# ADC_HUB.net
KiCad netlist of a schematic drawn in Altium Designer
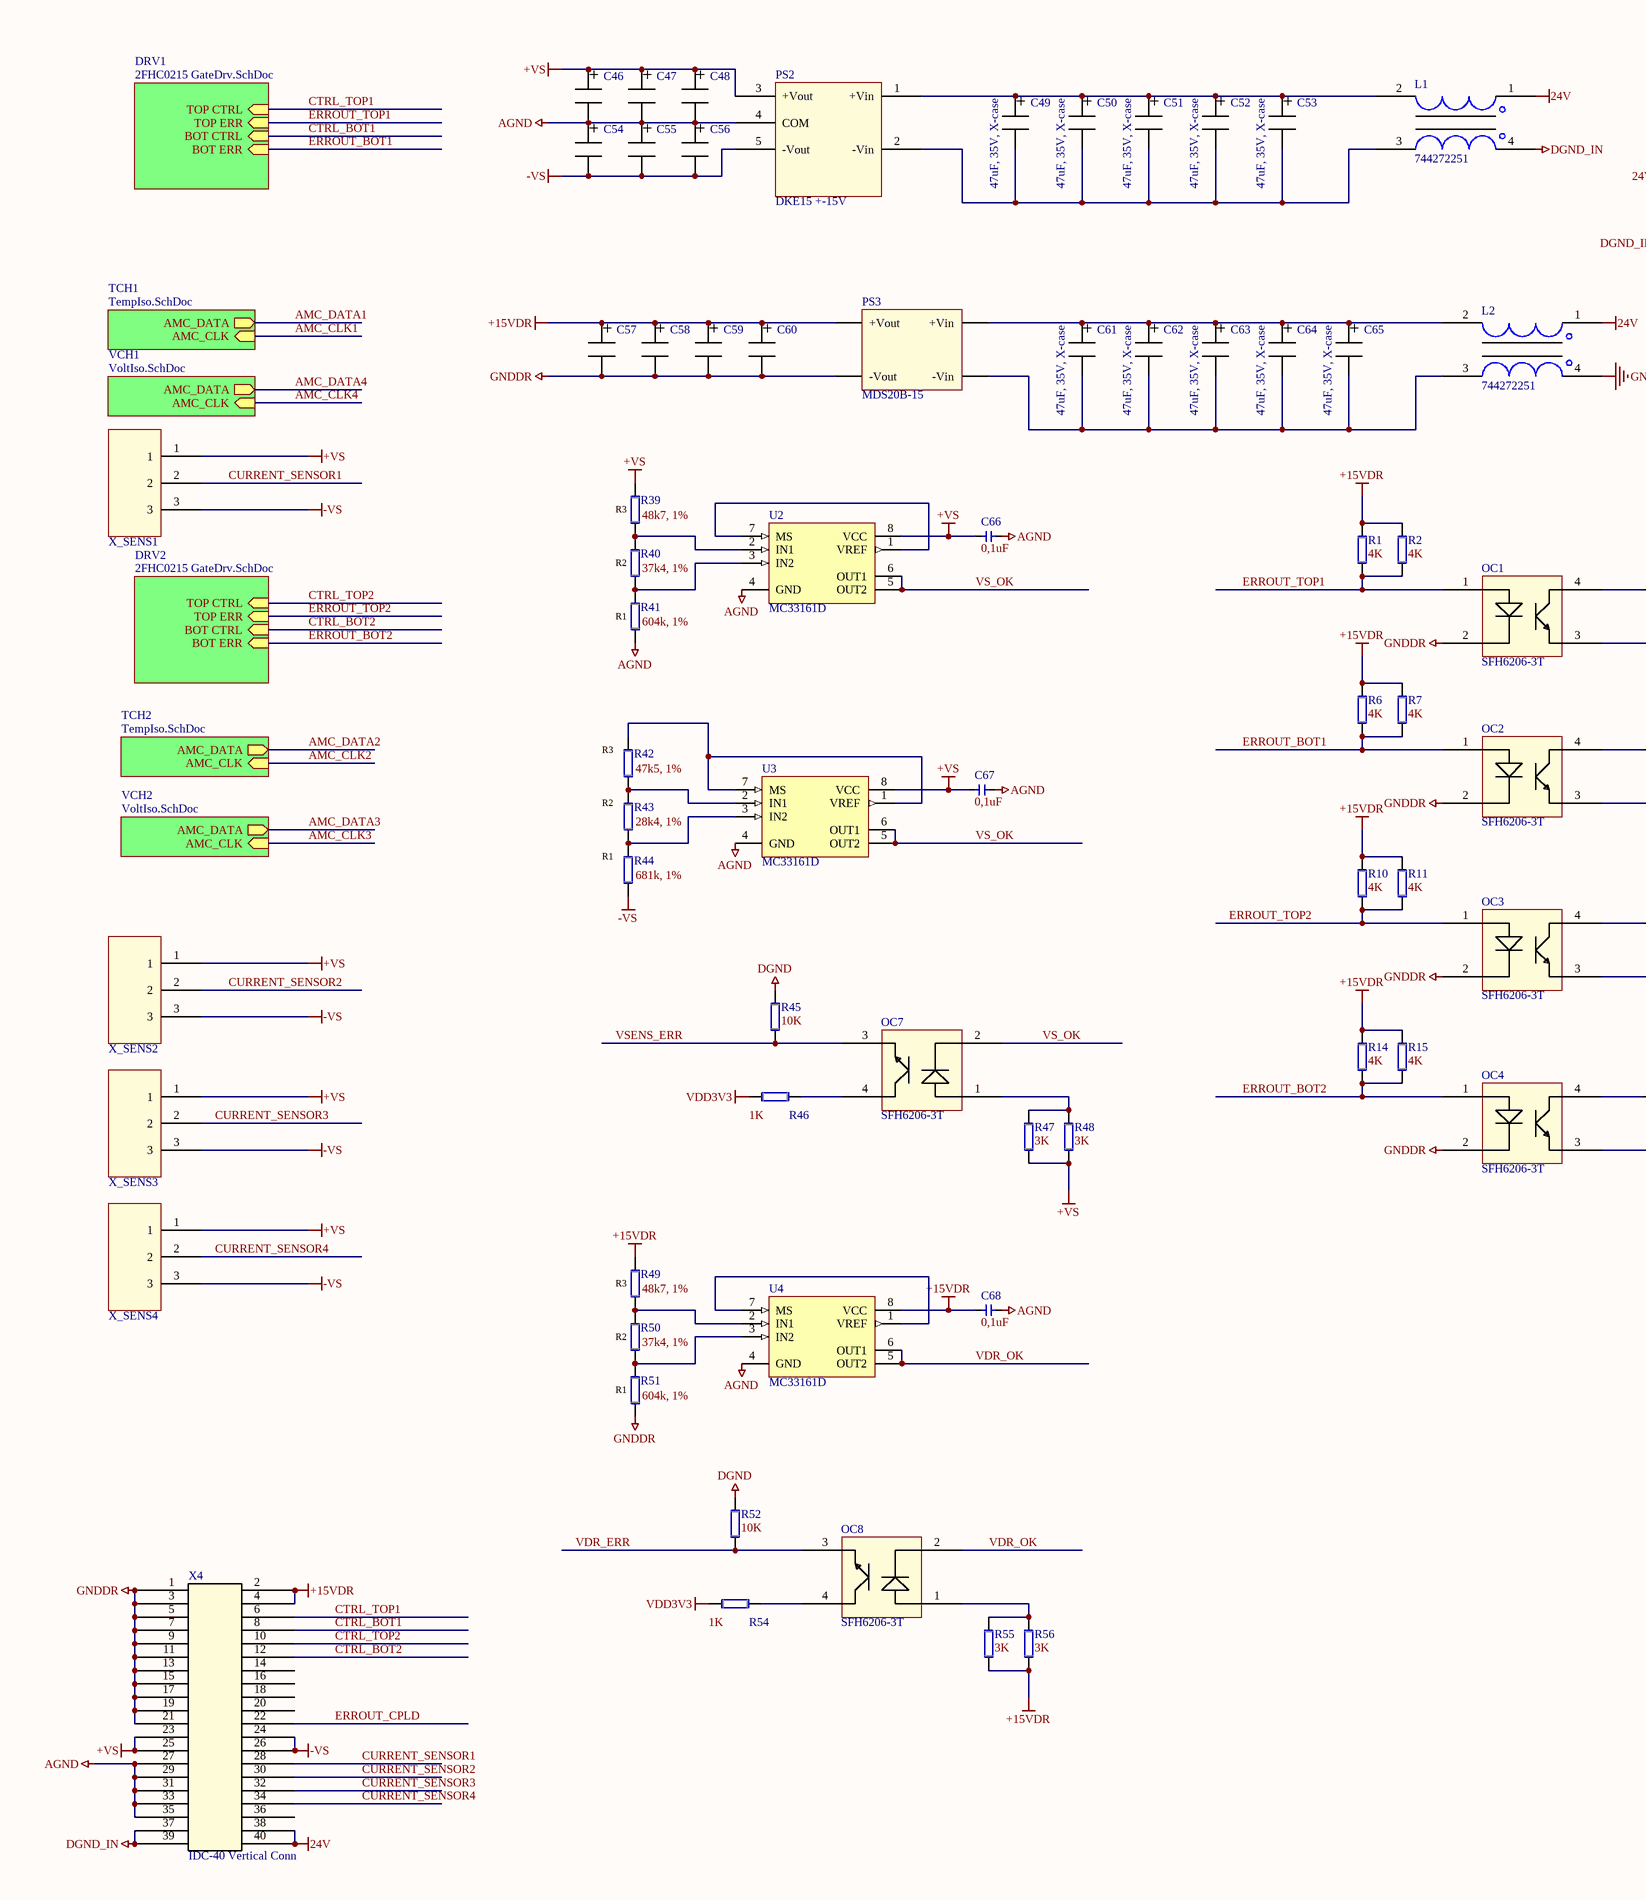
[diagram p0: ADC_HUB.SchDoc, left]
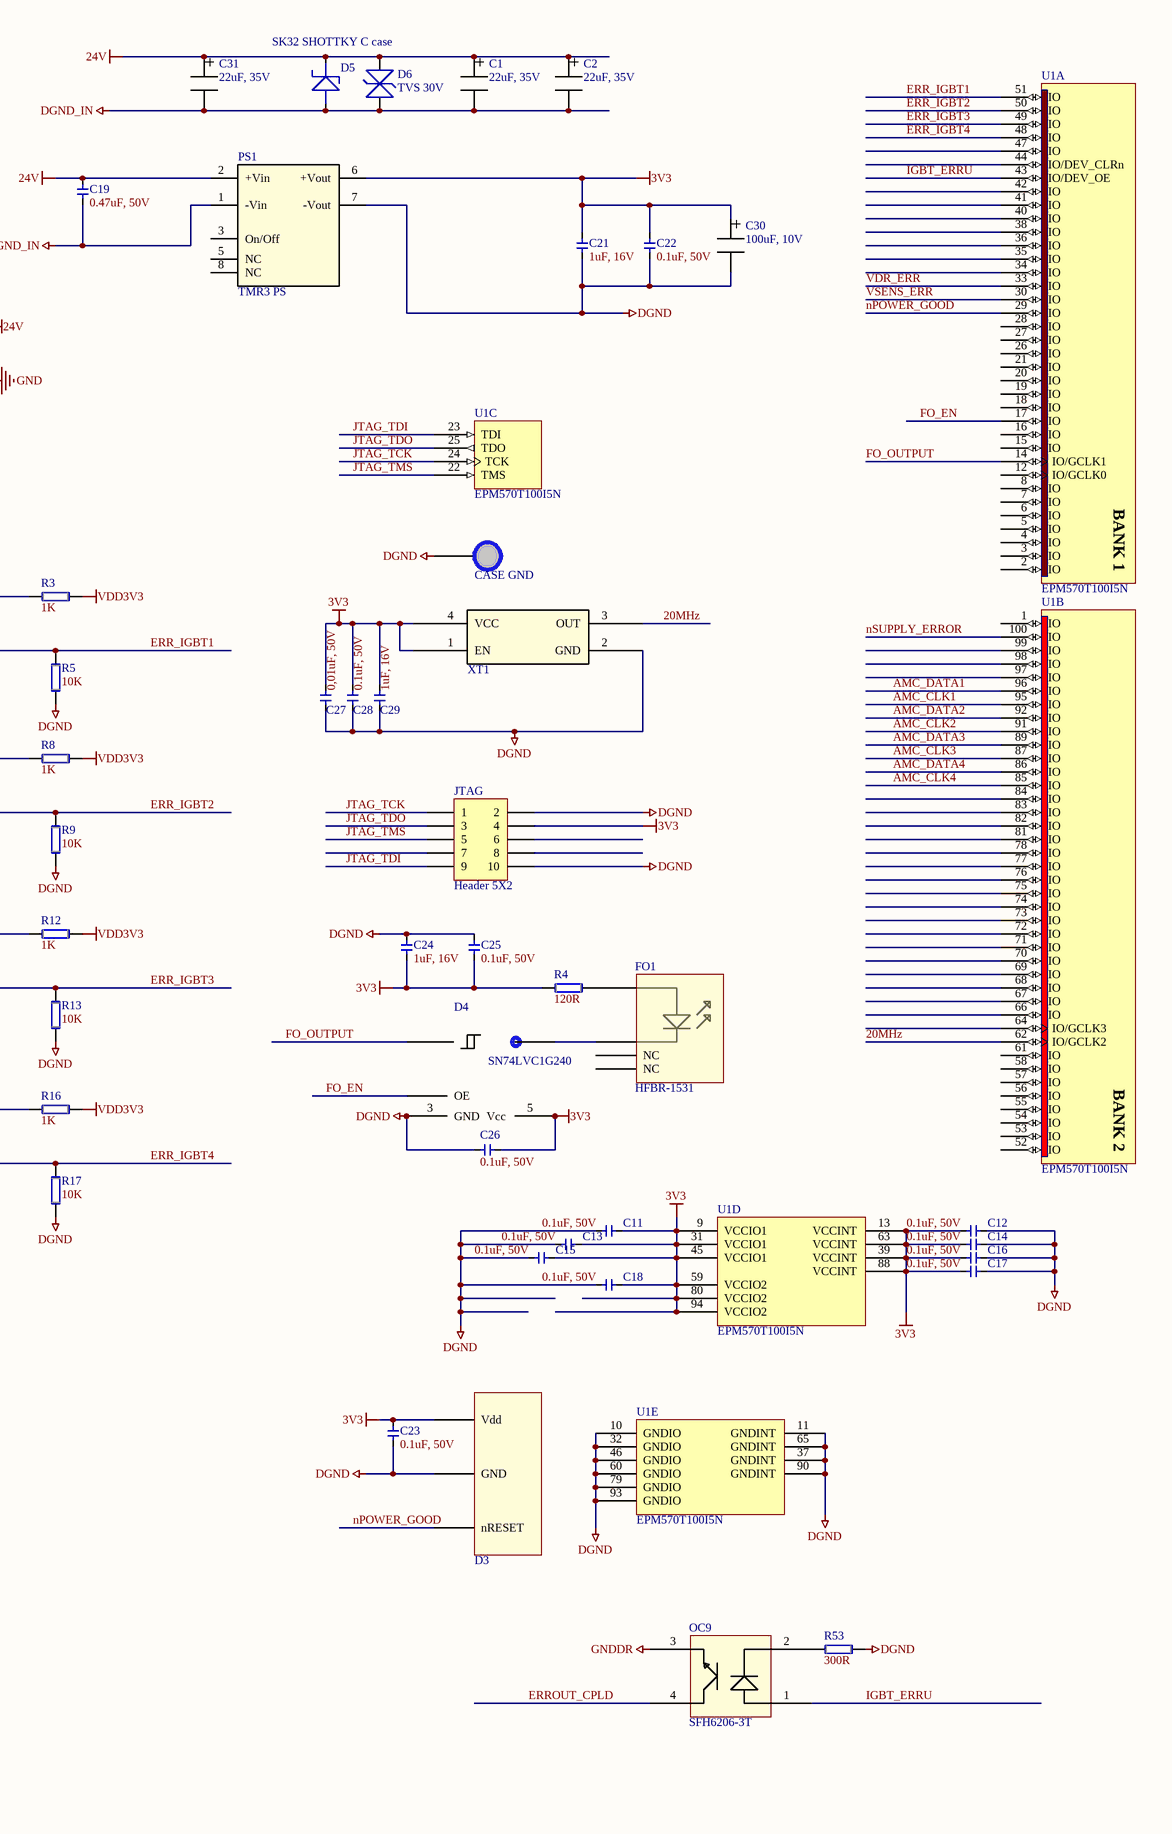
[diagram p1: ADC_HUB.SchDoc, right]

(export (version "E")
  (design (tool "Eeschema 10.0.6"))
  (components
    (comp (ref "C1")
      (value "22uF, 35V")
      (footprint "D")
      (fields (field (name "Comment") "Tant Cap D-case"))
      (libsource (lib "MyLib1") (part "C"))
    )
    (comp (ref "C2")
      (value "22uF, 35V")
      (footprint "D")
      (fields (field (name "Comment") "Tant Cap D-case"))
      (libsource (lib "MyLib1") (part "C"))
    )
    (comp (ref "C11")
      (value "0.1uF, 50V")
      (footprint "SMD CAP 0805")
      (fields (field (name "Comment") "ChipCap"))
      (libsource (lib "MyLib1") (part "ChipCapacitor"))
    )
    (comp (ref "C12")
      (value "0.1uF, 50V")
      (footprint "SMD CAP 0805")
      (fields (field (name "Comment") "ChipCap"))
      (libsource (lib "MyLib1") (part "ChipCapacitor"))
    )
    (comp (ref "C13")
      (value "0.1uF, 50V")
      (footprint "SMD CAP 0805")
      (fields (field (name "Comment") "ChipCap"))
      (libsource (lib "MyLib1") (part "ChipCapacitor"))
    )
    (comp (ref "C14")
      (value "0.1uF, 50V")
      (footprint "SMD CAP 0805")
      (fields (field (name "Comment") "ChipCap"))
      (libsource (lib "MyLib1") (part "ChipCapacitor"))
    )
    (comp (ref "C15")
      (value "0.1uF, 50V")
      (footprint "SMD CAP 0805")
      (fields (field (name "Comment") "ChipCap"))
      (libsource (lib "MyLib1") (part "ChipCapacitor"))
    )
    (comp (ref "C16")
      (value "0.1uF, 50V")
      (footprint "SMD CAP 0805")
      (fields (field (name "Comment") "ChipCap"))
      (libsource (lib "MyLib1") (part "ChipCapacitor"))
    )
    (comp (ref "C17")
      (value "0.1uF, 50V")
      (footprint "SMD CAP 0805")
      (fields (field (name "Comment") "ChipCap"))
      (libsource (lib "MyLib1") (part "ChipCapacitor"))
    )
    (comp (ref "C18")
      (value "0.1uF, 50V")
      (footprint "SMD CAP 0805")
      (fields (field (name "Comment") "ChipCap"))
      (libsource (lib "MyLib1") (part "ChipCapacitor"))
    )
    (comp (ref "C19")
      (value "0.47uF, 50V")
      (footprint "SMD CAP 0805")
      (fields (field (name "Comment") "ChipCap"))
      (libsource (lib "MyLib1") (part "ChipCapacitor"))
    )
    (comp (ref "C21")
      (value "1uF, 16V")
      (footprint "SMD CAP 0805")
      (fields (field (name "Comment") "ChipCap"))
      (libsource (lib "MyLib1") (part "ChipCapacitor"))
    )
    (comp (ref "C22")
      (value "0.1uF, 50V")
      (footprint "SMD CAP 0805")
      (fields (field (name "Comment") "ChipCap"))
      (libsource (lib "MyLib1") (part "ChipCapacitor"))
    )
    (comp (ref "C23")
      (value "0.1uF, 50V")
      (footprint "SMD CAP 0805")
      (fields (field (name "Comment") "ChipCap"))
      (libsource (lib "MyLib1") (part "ChipCapacitor"))
    )
    (comp (ref "C24")
      (value "1uF, 16V")
      (footprint "SMD CAP 0805")
      (fields (field (name "Comment") "ChipCap"))
      (libsource (lib "MyLib1") (part "ChipCapacitor"))
    )
    (comp (ref "C25")
      (value "0.1uF, 50V")
      (footprint "SMD CAP 0805")
      (fields (field (name "Comment") "ChipCap"))
      (libsource (lib "MyLib1") (part "ChipCapacitor"))
    )
    (comp (ref "C26")
      (value "0.1uF, 50V")
      (footprint "SMD CAP 0805")
      (fields (field (name "Comment") "ChipCap"))
      (libsource (lib "MyLib1") (part "ChipCapacitor"))
    )
    (comp (ref "C27")
      (value "0,01uF, 50V")
      (footprint "SMD CAP 0805")
      (fields (field (name "Comment") "ChipCap"))
      (libsource (lib "MyLib1") (part "ChipCapacitor"))
    )
    (comp (ref "C28")
      (value "0.1uF, 50V")
      (footprint "SMD CAP 0805")
      (fields (field (name "Comment") "ChipCap"))
      (libsource (lib "MyLib1") (part "ChipCapacitor"))
    )
    (comp (ref "C29")
      (value "1uF, 16V")
      (footprint "SMD CAP 0805")
      (fields (field (name "Comment") "ChipCap"))
      (libsource (lib "MyLib1") (part "ChipCapacitor"))
    )
    (comp (ref "C30")
      (value "100uF, 10V")
      (footprint "D")
      (fields (field (name "Comment") "Tant Cap D-case"))
      (libsource (lib "MyLib1") (part "C"))
    )
    (comp (ref "C31")
      (value "22uF, 35V")
      (footprint "D")
      (fields (field (name "Comment") "Tant Cap D-case"))
      (libsource (lib "MyLib1") (part "C"))
    )
    (comp (ref "C46") (value "Tant Cap D-case") (footprint "D") (libsource (lib "MyLib1") (part "C")))
    (comp (ref "C47") (value "Tant Cap D-case") (footprint "D") (libsource (lib "MyLib1") (part "C")))
    (comp (ref "C48") (value "Tant Cap D-case") (footprint "D") (libsource (lib "MyLib1") (part "C")))
    (comp (ref "C49")
      (value "47uF, 35V, X-case")
      (footprint "X")
      (fields (field (name "Comment") "Tant Cap D-case"))
      (libsource (lib "MyLib1") (part "C"))
    )
    (comp (ref "C50")
      (value "47uF, 35V, X-case")
      (footprint "X")
      (fields (field (name "Comment") "Tant Cap D-case"))
      (libsource (lib "MyLib1") (part "C"))
    )
    (comp (ref "C51")
      (value "47uF, 35V, X-case")
      (footprint "X")
      (fields (field (name "Comment") "Tant Cap D-case"))
      (libsource (lib "MyLib1") (part "C"))
    )
    (comp (ref "C52")
      (value "47uF, 35V, X-case")
      (footprint "X")
      (fields (field (name "Comment") "Tant Cap D-case"))
      (libsource (lib "MyLib1") (part "C"))
    )
    (comp (ref "C53")
      (value "47uF, 35V, X-case")
      (footprint "X")
      (fields (field (name "Comment") "Tant Cap D-case"))
      (libsource (lib "MyLib1") (part "C"))
    )
    (comp (ref "C54") (value "Tant Cap D-case") (footprint "D") (libsource (lib "MyLib1") (part "C")))
    (comp (ref "C55") (value "Tant Cap D-case") (footprint "D") (libsource (lib "MyLib1") (part "C")))
    (comp (ref "C56") (value "Tant Cap D-case") (footprint "D") (libsource (lib "MyLib1") (part "C")))
    (comp (ref "C57") (value "Tant Cap D-case") (footprint "D") (libsource (lib "MyLib1") (part "C")))
    (comp (ref "C58") (value "Tant Cap D-case") (footprint "D") (libsource (lib "MyLib1") (part "C")))
    (comp (ref "C59") (value "Tant Cap D-case") (footprint "D") (libsource (lib "MyLib1") (part "C")))
    (comp (ref "C60") (value "Tant Cap D-case") (footprint "D") (libsource (lib "MyLib1") (part "C")))
    (comp (ref "C61")
      (value "47uF, 35V, X-case")
      (footprint "X")
      (fields (field (name "Comment") "Tant Cap D-case"))
      (libsource (lib "MyLib1") (part "C"))
    )
    (comp (ref "C62")
      (value "47uF, 35V, X-case")
      (footprint "X")
      (fields (field (name "Comment") "Tant Cap D-case"))
      (libsource (lib "MyLib1") (part "C"))
    )
    (comp (ref "C63")
      (value "47uF, 35V, X-case")
      (footprint "X")
      (fields (field (name "Comment") "Tant Cap D-case"))
      (libsource (lib "MyLib1") (part "C"))
    )
    (comp (ref "C64")
      (value "47uF, 35V, X-case")
      (footprint "X")
      (fields (field (name "Comment") "Tant Cap D-case"))
      (libsource (lib "MyLib1") (part "C"))
    )
    (comp (ref "C65")
      (value "47uF, 35V, X-case")
      (footprint "X")
      (fields (field (name "Comment") "Tant Cap D-case"))
      (libsource (lib "MyLib1") (part "C"))
    )
    (comp (ref "C66")
      (value "0,1uF")
      (footprint "SMD CAP 0603")
      (fields (field (name "Comment") "ChipCap"))
      (libsource (lib "MyLib1") (part "ChipCapacitor"))
    )
    (comp (ref "C67")
      (value "0,1uF")
      (footprint "SMD CAP 0603")
      (fields (field (name "Comment") "ChipCap"))
      (libsource (lib "MyLib1") (part "ChipCapacitor"))
    )
    (comp (ref "C68")
      (value "0,1uF")
      (footprint "SMD CAP 0603")
      (fields (field (name "Comment") "ChipCap"))
      (libsource (lib "MyLib1") (part "ChipCapacitor"))
    )
    (comp (ref "CASE GND") (value "PAD 3mm") (footprint "PAD3mm") (libsource (lib "MyLib1") (part "PAD 3mm")))
    (comp (ref "D3")
      (value "TPS3809")
      (footprint "TPS3809")
      (description "Voltage Supervisor")
      (libsource (lib "MyLib1") (part "TPS3809"))
    )
    (comp (ref "D4")
      (value "SN74LVC1G240")
      (footprint "TI-SOT23 SOT95P280X145-5N")
      (description "Inverted Schmitt Trigger with EN")
      (libsource (lib "MyLib1") (part "SN74LVC1G240"))
    )
    (comp (ref "D5")
      (value "SK32 SHOTTKY C case")
      (footprint "SMC DIODE")
      (libsource (lib "MyLib1") (part "SK32 SHOTTKY"))
    )
    (comp (ref "D6")
      (value "TVS 30V")
      (footprint "SMB TVS")
      (libsource (lib "MyLib1") (part "SMB TVS BiDir"))
    )
    (comp (ref "FO1")
      (value "HFBR-1531")
      (footprint "1531/2531")
      (description "Fiber Optical Transmitter")
      (libsource (lib "MyLib1") (part "HFBR-1531"))
    )
    (comp (ref "JTAG")
      (value "Header 5X2")
      (footprint "HDR2X5")
      (description "Header, 5-Pin, Dual row")
      (fields (field (name "PUBLISHER") "Altium Limited"))
      (libsource (lib "Miscellaneous Connectors") (part "Header 5X2"))
    )
    (comp (ref "L1")
      (value "744272251")
      (footprint "744272251")
      (description "Wurth EMI Choke")
      (libsource (lib "MyLib1") (part "Wurth EMI Choke 744272251"))
    )
    (comp (ref "L2")
      (value "744272251")
      (footprint "744272251")
      (description "Wurth EMI Choke")
      (libsource (lib "MyLib1") (part "Wurth EMI Choke 744272251"))
    )
    (comp (ref "OC1")
      (value "SFH6206-3T")
      (footprint "SFH6206-3T")
      (description "SFH6206-3T Optocoupler")
      (libsource (lib "") (part "SFH6206-3T_1"))
    )
    (comp (ref "OC2")
      (value "SFH6206-3T")
      (footprint "SFH6206-3T")
      (description "SFH6206-3T Optocoupler")
      (libsource (lib "") (part "SFH6206-3T_1"))
    )
    (comp (ref "OC3")
      (value "SFH6206-3T")
      (footprint "SFH6206-3T")
      (description "SFH6206-3T Optocoupler")
      (libsource (lib "") (part "SFH6206-3T_1"))
    )
    (comp (ref "OC4")
      (value "SFH6206-3T")
      (footprint "SFH6206-3T")
      (description "SFH6206-3T Optocoupler")
      (libsource (lib "") (part "SFH6206-3T_1"))
    )
    (comp (ref "OC7")
      (value "SFH6206-3T")
      (footprint "SFH6206-3T")
      (description "SFH6206-3T Optocoupler")
      (libsource (lib "MyLib1") (part "SFH6206-3T"))
    )
    (comp (ref "OC8")
      (value "SFH6206-3T")
      (footprint "SFH6206-3T")
      (description "SFH6206-3T Optocoupler")
      (libsource (lib "MyLib1") (part "SFH6206-3T"))
    )
    (comp (ref "OC9")
      (value "SFH6206-3T")
      (footprint "SFH6206-3T")
      (description "SFH6206-3T Optocoupler")
      (libsource (lib "MyLib1") (part "SFH6206-3T"))
    )
    (comp (ref "PS1")
      (value "TMR3 PS")
      (footprint "TMR3 TRACO")
      (description "TMR3 power supply")
      (libsource (lib "MyLib1") (part "TMR3 TRACO"))
    )
    (comp (ref "PS2")
      (value "DKE15 +-15V")
      (footprint "DKE15")
      (description "DKE 15 MW Power Supply")
      (fields (field (name "Comment") "DKE 15 PS"))
      (libsource (lib "MyLib1") (part "DKE15 PS"))
    )
    (comp (ref "PS3")
      (value "MDS20B-15")
      (footprint "MDS20B-15")
      (description "MDS20B-15  power supply 15V")
      (libsource (lib "MyLib1") (part "MDS20B-15"))
    )
    (comp (ref "R1")
      (value "4K")
      (footprint "R1206")
      (fields (field (name "Comment") "Rsize"))
      (libsource (lib "MyLib1") (part "ChipResistor"))
    )
    (comp (ref "R2")
      (value "4K")
      (footprint "R1206")
      (fields (field (name "Comment") "Rsize"))
      (libsource (lib "MyLib1") (part "ChipResistor"))
    )
    (comp (ref "R3")
      (value "1K")
      (footprint "SMD RES 0805")
      (fields (field (name "Comment") "Rsize"))
      (libsource (lib "MyLib1") (part "ChipResistor"))
    )
    (comp (ref "R4")
      (value "120R")
      (footprint "SMD RES 0805")
      (fields (field (name "Comment") "Rsize"))
      (libsource (lib "MyLib1") (part "ChipResistor"))
    )
    (comp (ref "R5")
      (value "10K")
      (footprint "SMD RES 0805")
      (fields (field (name "Comment") "Rsize"))
      (libsource (lib "MyLib1") (part "ChipResistor"))
    )
    (comp (ref "R6")
      (value "4K")
      (footprint "R1206")
      (fields (field (name "Comment") "Rsize"))
      (libsource (lib "MyLib1") (part "ChipResistor"))
    )
    (comp (ref "R7")
      (value "4K")
      (footprint "R1206")
      (fields (field (name "Comment") "Rsize"))
      (libsource (lib "MyLib1") (part "ChipResistor"))
    )
    (comp (ref "R8")
      (value "1K")
      (footprint "SMD RES 0805")
      (fields (field (name "Comment") "Rsize"))
      (libsource (lib "MyLib1") (part "ChipResistor"))
    )
    (comp (ref "R9")
      (value "10K")
      (footprint "SMD RES 0805")
      (fields (field (name "Comment") "Rsize"))
      (libsource (lib "MyLib1") (part "ChipResistor"))
    )
    (comp (ref "R10")
      (value "4K")
      (footprint "R1206")
      (fields (field (name "Comment") "Rsize"))
      (libsource (lib "MyLib1") (part "ChipResistor"))
    )
    (comp (ref "R11")
      (value "4K")
      (footprint "R1206")
      (fields (field (name "Comment") "Rsize"))
      (libsource (lib "MyLib1") (part "ChipResistor"))
    )
    (comp (ref "R12")
      (value "1K")
      (footprint "SMD RES 0805")
      (fields (field (name "Comment") "Rsize"))
      (libsource (lib "MyLib1") (part "ChipResistor"))
    )
    (comp (ref "R13")
      (value "10K")
      (footprint "SMD RES 0805")
      (fields (field (name "Comment") "Rsize"))
      (libsource (lib "MyLib1") (part "ChipResistor"))
    )
    (comp (ref "R14")
      (value "4K")
      (footprint "R1206")
      (fields (field (name "Comment") "Rsize"))
      (libsource (lib "MyLib1") (part "ChipResistor"))
    )
    (comp (ref "R15")
      (value "4K")
      (footprint "R1206")
      (fields (field (name "Comment") "Rsize"))
      (libsource (lib "MyLib1") (part "ChipResistor"))
    )
    (comp (ref "R16")
      (value "1K")
      (footprint "SMD RES 0805")
      (fields (field (name "Comment") "Rsize"))
      (libsource (lib "MyLib1") (part "ChipResistor"))
    )
    (comp (ref "R17")
      (value "10K")
      (footprint "SMD RES 0805")
      (fields (field (name "Comment") "Rsize"))
      (libsource (lib "MyLib1") (part "ChipResistor"))
    )
    (comp (ref "R39")
      (value "48k7, 1%")
      (footprint "SMD RES 0603")
      (fields (field (name "Comment") "Rsize"))
      (libsource (lib "MyLib1") (part "ChipResistor"))
    )
    (comp (ref "R40")
      (value "37k4, 1%")
      (footprint "SMD RES 0603")
      (fields (field (name "Comment") "Rsize"))
      (libsource (lib "MyLib1") (part "ChipResistor"))
    )
    (comp (ref "R41")
      (value "604k, 1%")
      (footprint "SMD RES 0603")
      (fields (field (name "Comment") "Rsize"))
      (libsource (lib "MyLib1") (part "ChipResistor"))
    )
    (comp (ref "R42")
      (value "47k5, 1%")
      (footprint "SMD RES 0603")
      (fields (field (name "Comment") "Rsize"))
      (libsource (lib "MyLib1") (part "ChipResistor"))
    )
    (comp (ref "R43")
      (value "28k4, 1%")
      (footprint "SMD RES 0603")
      (fields (field (name "Comment") "Rsize"))
      (libsource (lib "MyLib1") (part "ChipResistor"))
    )
    (comp (ref "R44")
      (value "681k, 1%")
      (footprint "SMD RES 0603")
      (fields (field (name "Comment") "Rsize"))
      (libsource (lib "MyLib1") (part "ChipResistor"))
    )
    (comp (ref "R45")
      (value "10K")
      (footprint "SMD RES 0805")
      (fields (field (name "Comment") "Rsize"))
      (libsource (lib "MyLib1") (part "ChipResistor"))
    )
    (comp (ref "R46")
      (value "1K")
      (footprint "SMD RES 0805")
      (fields (field (name "Comment") "Rsize"))
      (libsource (lib "MyLib1") (part "ChipResistor"))
    )
    (comp (ref "R47")
      (value "3K")
      (footprint "R1206")
      (fields (field (name "Comment") "Rsize"))
      (libsource (lib "MyLib1") (part "ChipResistor"))
    )
    (comp (ref "R48")
      (value "3K")
      (footprint "R1206")
      (fields (field (name "Comment") "Rsize"))
      (libsource (lib "MyLib1") (part "ChipResistor"))
    )
    (comp (ref "R49")
      (value "48k7, 1%")
      (footprint "SMD RES 0603")
      (fields (field (name "Comment") "Rsize"))
      (libsource (lib "MyLib1") (part "ChipResistor"))
    )
    (comp (ref "R50")
      (value "37k4, 1%")
      (footprint "SMD RES 0603")
      (fields (field (name "Comment") "Rsize"))
      (libsource (lib "MyLib1") (part "ChipResistor"))
    )
    (comp (ref "R51")
      (value "604k, 1%")
      (footprint "SMD RES 0603")
      (fields (field (name "Comment") "Rsize"))
      (libsource (lib "MyLib1") (part "ChipResistor"))
    )
    (comp (ref "R52")
      (value "10K")
      (footprint "SMD RES 0805")
      (fields (field (name "Comment") "Rsize"))
      (libsource (lib "MyLib1") (part "ChipResistor"))
    )
    (comp (ref "R53")
      (value "300R")
      (footprint "R1206")
      (fields (field (name "Comment") "Rsize"))
      (libsource (lib "MyLib1") (part "ChipResistor"))
    )
    (comp (ref "R54")
      (value "1K")
      (footprint "SMD RES 0805")
      (fields (field (name "Comment") "Rsize"))
      (libsource (lib "MyLib1") (part "ChipResistor"))
    )
    (comp (ref "R55")
      (value "3K")
      (footprint "R1206")
      (fields (field (name "Comment") "Rsize"))
      (libsource (lib "MyLib1") (part "ChipResistor"))
    )
    (comp (ref "R56")
      (value "3K")
      (footprint "R1206")
      (fields (field (name "Comment") "Rsize"))
      (libsource (lib "MyLib1") (part "ChipResistor"))
    )
    (comp (ref "U1")
      (value "EPM570T100I5N")
      (footprint "TQFP100_N")
      (fields (field (name "PUBLISHER") "Altium Limited"))
      (libsource (lib "Altera MAX II") (part "EPM570T100I5N"))
    )
    (comp (ref "U2")
      (value "MC33161D")
      (footprint "751-05_N")
      (description "Universal Voltage Monitor")
      (fields (field (name "PUBLISHER") "Altium Limited"))
      (libsource (lib "ON Semi Power Mgt Voltage Detector") (part "MC33161D"))
    )
    (comp (ref "U3")
      (value "MC33161D")
      (footprint "751-05_N")
      (description "Universal Voltage Monitor")
      (fields (field (name "PUBLISHER") "Altium Limited"))
      (libsource (lib "ON Semi Power Mgt Voltage Detector") (part "MC33161D"))
    )
    (comp (ref "U4")
      (value "MC33161D")
      (footprint "751-05_N")
      (description "Universal Voltage Monitor")
      (fields (field (name "PUBLISHER") "Altium Limited"))
      (libsource (lib "ON Semi Power Mgt Voltage Detector") (part "MC33161D"))
    )
    (comp (ref "X4")
      (value "IDC-40 Vertical Conn")
      (footprint "IDC2.54-V40")
      (libsource (lib "MyLib1") (part "IDC-40"))
    )
    (comp (ref "XT1")
      (value "Crystal generator")
      (footprint "OSC3225 YXC")
      (libsource (lib "MyLib1") (part "GEN 0532"))
    )
    (comp (ref "X_SENS1")
      (value "Connector 3.5mm")
      (footprint "15EDGRC-3.5 3P")
      (libsource (lib "MyLib1") (part "15EDGRC-3.5 3P"))
    )
    (comp (ref "X_SENS2")
      (value "Connector 3.5mm")
      (footprint "15EDGRC-3.5 3P")
      (libsource (lib "MyLib1") (part "15EDGRC-3.5 3P"))
    )
    (comp (ref "X_SENS3")
      (value "Connector 3.5mm")
      (footprint "15EDGRC-3.5 3P")
      (libsource (lib "MyLib1") (part "15EDGRC-3.5 3P"))
    )
    (comp (ref "X_SENS4")
      (value "Connector 3.5mm")
      (footprint "15EDGRC-3.5 3P")
      (libsource (lib "MyLib1") (part "15EDGRC-3.5 3P"))
    )
  )
  (nets
    (net (code "1") (name "+15VDR") (class "Default")
      (node (ref "C57") (pin "1") (pinfunction "1_1") (pintype "passive"))
      (node (ref "C58") (pin "1") (pinfunction "1_1") (pintype "passive"))
      (node (ref "C59") (pin "1") (pinfunction "1_1") (pintype "passive"))
      (node (ref "C60") (pin "1") (pinfunction "1_1") (pintype "passive"))
      (node (ref "C68") (pin "2") (pinfunction "2_2") (pintype "passive"))
      (node (ref "PS3") (pin "3") (pinfunction "+Vout_3") (pintype "passive"))
      (node (ref "R1") (pin "1") (pinfunction "1_1") (pintype "passive"))
      (node (ref "R10") (pin "1") (pinfunction "1_1") (pintype "passive"))
      (node (ref "R11") (pin "1") (pinfunction "1_1") (pintype "passive"))
      (node (ref "R14") (pin "1") (pinfunction "1_1") (pintype "passive"))
      (node (ref "R15") (pin "1") (pinfunction "1_1") (pintype "passive"))
      (node (ref "R2") (pin "1") (pinfunction "1_1") (pintype "passive"))
      (node (ref "R49") (pin "1") (pinfunction "1_1") (pintype "passive"))
      (node (ref "R55") (pin "1") (pinfunction "1_1") (pintype "passive"))
      (node (ref "R56") (pin "1") (pinfunction "1_1") (pintype "passive"))
      (node (ref "R6") (pin "1") (pinfunction "1_1") (pintype "passive"))
      (node (ref "R7") (pin "1") (pinfunction "1_1") (pintype "passive"))
      (node (ref "U4") (pin "8") (pinfunction "VCC_8") (pintype "power_in"))
      (node (ref "X4") (pin "2") (pinfunction "2_2") (pintype "passive"))
      (node (ref "X4") (pin "4") (pinfunction "4_4") (pintype "passive"))
    )
    (net (code "2") (name "+VS") (class "Default")
      (node (ref "C46") (pin "1") (pinfunction "1_1") (pintype "passive"))
      (node (ref "C47") (pin "1") (pinfunction "1_1") (pintype "passive"))
      (node (ref "C48") (pin "1") (pinfunction "1_1") (pintype "passive"))
      (node (ref "C66") (pin "2") (pinfunction "2_2") (pintype "passive"))
      (node (ref "C67") (pin "2") (pinfunction "2_2") (pintype "passive"))
      (node (ref "PS2") (pin "3") (pinfunction "+Vout_3") (pintype "passive"))
      (node (ref "R39") (pin "1") (pinfunction "1_1") (pintype "passive"))
      (node (ref "R47") (pin "1") (pinfunction "1_1") (pintype "passive"))
      (node (ref "R48") (pin "1") (pinfunction "1_1") (pintype "passive"))
      (node (ref "U2") (pin "8") (pinfunction "VCC_8") (pintype "power_in"))
      (node (ref "U3") (pin "8") (pinfunction "VCC_8") (pintype "power_in"))
      (node (ref "X4") (pin "23") (pinfunction "23_23") (pintype "passive"))
      (node (ref "X4") (pin "25") (pinfunction "25_25") (pintype "passive"))
      (node (ref "X_SENS1") (pin "1") (pinfunction "1_1") (pintype "passive"))
      (node (ref "X_SENS2") (pin "1") (pinfunction "1_1") (pintype "passive"))
      (node (ref "X_SENS3") (pin "1") (pinfunction "1_1") (pintype "passive"))
      (node (ref "X_SENS4") (pin "1") (pinfunction "1_1") (pintype "passive"))
    )
    (net (code "3") (name "-VS") (class "Default")
      (node (ref "C54") (pin "2") (pinfunction "2_2") (pintype "passive"))
      (node (ref "C55") (pin "2") (pinfunction "2_2") (pintype "passive"))
      (node (ref "C56") (pin "2") (pinfunction "2_2") (pintype "passive"))
      (node (ref "PS2") (pin "5") (pinfunction "-Vout_5") (pintype "passive"))
      (node (ref "R44") (pin "2") (pinfunction "2_2") (pintype "passive"))
      (node (ref "X4") (pin "24") (pinfunction "24_24") (pintype "passive"))
      (node (ref "X4") (pin "26") (pinfunction "26_26") (pintype "passive"))
      (node (ref "X_SENS1") (pin "3") (pinfunction "3_3") (pintype "passive"))
      (node (ref "X_SENS2") (pin "3") (pinfunction "3_3") (pintype "passive"))
      (node (ref "X_SENS3") (pin "3") (pinfunction "3_3") (pintype "passive"))
      (node (ref "X_SENS4") (pin "3") (pinfunction "3_3") (pintype "passive"))
    )
    (net (code "4") (name "/20MHz") (class "Default")
      (node (ref "U1") (pin "62") (pinfunction "IO/GCLK2_62") (pintype "bidirectional"))
      (node (ref "XT1") (pin "3") (pinfunction "OUT_3") (pintype "passive"))
    )
    (net (code "5") (name "/AMC_CLK1") (class "Default")
      (node (ref "U1") (pin "95") (pinfunction "IO_95") (pintype "bidirectional"))
    )
    (net (code "6") (name "/AMC_CLK2") (class "Default")
      (node (ref "U1") (pin "91") (pinfunction "IO_91") (pintype "bidirectional"))
    )
    (net (code "7") (name "/AMC_CLK3") (class "Default")
      (node (ref "U1") (pin "87") (pinfunction "IO_87") (pintype "bidirectional"))
    )
    (net (code "8") (name "/AMC_CLK4") (class "Default")
      (node (ref "U1") (pin "85") (pinfunction "IO_85") (pintype "bidirectional"))
    )
    (net (code "9") (name "/AMC_DATA1") (class "Default")
      (node (ref "U1") (pin "96") (pinfunction "IO_96") (pintype "bidirectional"))
    )
    (net (code "10") (name "/AMC_DATA2") (class "Default")
      (node (ref "U1") (pin "92") (pinfunction "IO_92") (pintype "bidirectional"))
    )
    (net (code "11") (name "/AMC_DATA3") (class "Default")
      (node (ref "U1") (pin "89") (pinfunction "IO_89") (pintype "bidirectional"))
    )
    (net (code "12") (name "/AMC_DATA4") (class "Default")
      (node (ref "U1") (pin "86") (pinfunction "IO_86") (pintype "bidirectional"))
    )
    (net (code "13") (name "/CTRL_BOT1") (class "Default")
      (node (ref "X4") (pin "8") (pinfunction "8_8") (pintype "passive"))
    )
    (net (code "14") (name "/CTRL_BOT2") (class "Default")
      (node (ref "X4") (pin "12") (pinfunction "12_12") (pintype "passive"))
    )
    (net (code "15") (name "/CTRL_TOP1") (class "Default")
      (node (ref "X4") (pin "6") (pinfunction "6_6") (pintype "passive"))
    )
    (net (code "16") (name "/CTRL_TOP2") (class "Default")
      (node (ref "X4") (pin "10") (pinfunction "10_10") (pintype "passive"))
    )
    (net (code "17") (name "/CURRENT_SENSOR1") (class "Default")
      (node (ref "X4") (pin "28") (pinfunction "28_28") (pintype "passive"))
      (node (ref "X_SENS1") (pin "2") (pinfunction "2_2") (pintype "passive"))
    )
    (net (code "18") (name "/CURRENT_SENSOR2") (class "Default")
      (node (ref "X4") (pin "30") (pinfunction "30_30") (pintype "passive"))
      (node (ref "X_SENS2") (pin "2") (pinfunction "2_2") (pintype "passive"))
    )
    (net (code "19") (name "/CURRENT_SENSOR3") (class "Default")
      (node (ref "X4") (pin "32") (pinfunction "32_32") (pintype "passive"))
      (node (ref "X_SENS3") (pin "2") (pinfunction "2_2") (pintype "passive"))
    )
    (net (code "20") (name "/CURRENT_SENSOR4") (class "Default")
      (node (ref "X4") (pin "34") (pinfunction "34_34") (pintype "passive"))
      (node (ref "X_SENS4") (pin "2") (pinfunction "2_2") (pintype "passive"))
    )
    (net (code "21") (name "/ERROUT_BOT1") (class "Default")
      (node (ref "OC2") (pin "1") (pinfunction "1_1") (pintype "passive"))
      (node (ref "R6") (pin "2") (pinfunction "2_2") (pintype "passive"))
      (node (ref "R7") (pin "2") (pinfunction "2_2") (pintype "passive"))
    )
    (net (code "22") (name "/ERROUT_BOT2") (class "Default")
      (node (ref "OC4") (pin "1") (pinfunction "1_1") (pintype "passive"))
      (node (ref "R14") (pin "2") (pinfunction "2_2") (pintype "passive"))
      (node (ref "R15") (pin "2") (pinfunction "2_2") (pintype "passive"))
    )
    (net (code "23") (name "/ERROUT_CPLD") (class "Default")
      (node (ref "OC9") (pin "4") (pinfunction "4_4") (pintype "passive"))
      (node (ref "X4") (pin "22") (pinfunction "22_22") (pintype "passive"))
    )
    (net (code "24") (name "/ERROUT_TOP1") (class "Default")
      (node (ref "OC1") (pin "1") (pinfunction "1_1") (pintype "passive"))
      (node (ref "R1") (pin "2") (pinfunction "2_2") (pintype "passive"))
      (node (ref "R2") (pin "2") (pinfunction "2_2") (pintype "passive"))
    )
    (net (code "25") (name "/ERROUT_TOP2") (class "Default")
      (node (ref "OC3") (pin "1") (pinfunction "1_1") (pintype "passive"))
      (node (ref "R10") (pin "2") (pinfunction "2_2") (pintype "passive"))
      (node (ref "R11") (pin "2") (pinfunction "2_2") (pintype "passive"))
    )
    (net (code "26") (name "/ERR_IGBT1") (class "Default")
      (node (ref "OC1") (pin "3") (pinfunction "3_3") (pintype "passive"))
      (node (ref "R5") (pin "2") (pinfunction "2_2") (pintype "passive"))
      (node (ref "U1") (pin "51") (pinfunction "IO_51") (pintype "bidirectional"))
    )
    (net (code "27") (name "/ERR_IGBT2") (class "Default")
      (node (ref "OC2") (pin "3") (pinfunction "3_3") (pintype "passive"))
      (node (ref "R9") (pin "2") (pinfunction "2_2") (pintype "passive"))
      (node (ref "U1") (pin "50") (pinfunction "IO_50") (pintype "bidirectional"))
    )
    (net (code "28") (name "/ERR_IGBT3") (class "Default")
      (node (ref "OC3") (pin "3") (pinfunction "3_3") (pintype "passive"))
      (node (ref "R13") (pin "2") (pinfunction "2_2") (pintype "passive"))
      (node (ref "U1") (pin "49") (pinfunction "IO_49") (pintype "bidirectional"))
    )
    (net (code "29") (name "/ERR_IGBT4") (class "Default")
      (node (ref "OC4") (pin "3") (pinfunction "3_3") (pintype "passive"))
      (node (ref "R17") (pin "2") (pinfunction "2_2") (pintype "passive"))
      (node (ref "U1") (pin "48") (pinfunction "IO_48") (pintype "bidirectional"))
    )
    (net (code "30") (name "/FO_EN") (class "Default")
      (node (ref "D4") (pin "1") (pinfunction "OE_1") (pintype "passive"))
      (node (ref "U1") (pin "17") (pinfunction "IO_17") (pintype "bidirectional"))
    )
    (net (code "31") (name "/FO_OUTPUT") (class "Default")
      (node (ref "D4") (pin "2") (pinfunction "A_2") (pintype "passive"))
      (node (ref "U1") (pin "14") (pinfunction "IO/GCLK1_14") (pintype "bidirectional"))
    )
    (net (code "32") (name "/IGBT_ERRU") (class "Default")
      (node (ref "OC9") (pin "1") (pinfunction "1_1") (pintype "passive"))
      (node (ref "U1") (pin "43") (pinfunction "IO/DEV_OE_43") (pintype "bidirectional"))
    )
    (net (code "33") (name "/JTAG_TCK") (class "Default")
      (node (ref "JTAG") (pin "1") (pinfunction "1_1") (pintype "passive"))
      (node (ref "U1") (pin "24") (pinfunction "TCK_24") (pintype "input"))
    )
    (net (code "34") (name "/JTAG_TDI") (class "Default")
      (node (ref "JTAG") (pin "9") (pinfunction "9_9") (pintype "passive"))
      (node (ref "U1") (pin "23") (pinfunction "TDI_23") (pintype "input"))
    )
    (net (code "35") (name "/JTAG_TDO") (class "Default")
      (node (ref "JTAG") (pin "3") (pinfunction "3_3") (pintype "passive"))
      (node (ref "U1") (pin "25") (pinfunction "TDO_25") (pintype "output"))
    )
    (net (code "36") (name "/JTAG_TMS") (class "Default")
      (node (ref "JTAG") (pin "5") (pinfunction "5_5") (pintype "passive"))
      (node (ref "U1") (pin "22") (pinfunction "TMS_22") (pintype "input"))
    )
    (net (code "37") (name "/VDR_ERR") (class "Default")
      (node (ref "OC8") (pin "3") (pinfunction "3_3") (pintype "passive"))
      (node (ref "R52") (pin "2") (pinfunction "2_2") (pintype "passive"))
      (node (ref "U1") (pin "33") (pinfunction "IO_33") (pintype "bidirectional"))
    )
    (net (code "38") (name "/VDR_OK") (class "Default")
      (node (ref "OC8") (pin "2") (pinfunction "2_2") (pintype "passive"))
      (node (ref "U4") (pin "5") (pinfunction "OUT2_5") (pintype "open_collector"))
      (node (ref "U4") (pin "6") (pinfunction "OUT1_6") (pintype "open_collector"))
    )
    (net (code "39") (name "/VSENS_ERR") (class "Default")
      (node (ref "OC7") (pin "3") (pinfunction "3_3") (pintype "passive"))
      (node (ref "R45") (pin "2") (pinfunction "2_2") (pintype "passive"))
      (node (ref "U1") (pin "30") (pinfunction "IO_30") (pintype "bidirectional"))
    )
    (net (code "40") (name "/VS_OK") (class "Default")
      (node (ref "OC7") (pin "2") (pinfunction "2_2") (pintype "passive"))
      (node (ref "U2") (pin "5") (pinfunction "OUT2_5") (pintype "open_collector"))
      (node (ref "U2") (pin "6") (pinfunction "OUT1_6") (pintype "open_collector"))
      (node (ref "U3") (pin "5") (pinfunction "OUT2_5") (pintype "open_collector"))
      (node (ref "U3") (pin "6") (pinfunction "OUT1_6") (pintype "open_collector"))
    )
    (net (code "41") (name "/nPOWER_GOOD") (class "Default")
      (node (ref "D3") (pin "2") (pinfunction "nRESET_2") (pintype "passive"))
      (node (ref "U1") (pin "29") (pinfunction "IO_29") (pintype "bidirectional"))
    )
    (net (code "42") (name "/nSUPPLY_ERROR") (class "Default")
      (node (ref "U1") (pin "100") (pinfunction "IO_100") (pintype "bidirectional"))
    )
    (net (code "43") (name "3V3") (class "Default")
      (node (ref "C11") (pin "1") (pinfunction "1_1") (pintype "passive"))
      (node (ref "C12") (pin "2") (pinfunction "2_2") (pintype "passive"))
      (node (ref "C13") (pin "1") (pinfunction "1_1") (pintype "passive"))
      (node (ref "C14") (pin "2") (pinfunction "2_2") (pintype "passive"))
      (node (ref "C15") (pin "1") (pinfunction "1_1") (pintype "passive"))
      (node (ref "C16") (pin "2") (pinfunction "2_2") (pintype "passive"))
      (node (ref "C17") (pin "2") (pinfunction "2_2") (pintype "passive"))
      (node (ref "C18") (pin "1") (pinfunction "1_1") (pintype "passive"))
      (node (ref "C21") (pin "1") (pinfunction "1_1") (pintype "passive"))
      (node (ref "C22") (pin "1") (pinfunction "1_1") (pintype "passive"))
      (node (ref "C23") (pin "1") (pinfunction "1_1") (pintype "passive"))
      (node (ref "C24") (pin "2") (pinfunction "2_2") (pintype "passive"))
      (node (ref "C25") (pin "2") (pinfunction "2_2") (pintype "passive"))
      (node (ref "C26") (pin "2") (pinfunction "2_2") (pintype "passive"))
      (node (ref "C27") (pin "1") (pinfunction "1_1") (pintype "passive"))
      (node (ref "C28") (pin "1") (pinfunction "1_1") (pintype "passive"))
      (node (ref "C29") (pin "1") (pinfunction "1_1") (pintype "passive"))
      (node (ref "C30") (pin "1") (pinfunction "1_1") (pintype "passive"))
      (node (ref "D3") (pin "3") (pinfunction "Vdd_3") (pintype "passive"))
      (node (ref "D4") (pin "5") (pinfunction "Vcc_5") (pintype "passive"))
      (node (ref "JTAG") (pin "4") (pinfunction "4_4") (pintype "passive"))
      (node (ref "PS1") (pin "6") (pinfunction "+Vout_6") (pintype "passive"))
      (node (ref "R4") (pin "2") (pinfunction "2_2") (pintype "passive"))
      (node (ref "U1") (pin "13") (pinfunction "VCCINT_13") (pintype "power_in"))
      (node (ref "U1") (pin "31") (pinfunction "VCCIO1_31") (pintype "power_in"))
      (node (ref "U1") (pin "39") (pinfunction "VCCINT_39") (pintype "power_in"))
      (node (ref "U1") (pin "45") (pinfunction "VCCIO1_45") (pintype "power_in"))
      (node (ref "U1") (pin "59") (pinfunction "VCCIO2_59") (pintype "power_in"))
      (node (ref "U1") (pin "63") (pinfunction "VCCINT_63") (pintype "power_in"))
      (node (ref "U1") (pin "80") (pinfunction "VCCIO2_80") (pintype "power_in"))
      (node (ref "U1") (pin "88") (pinfunction "VCCINT_88") (pintype "power_in"))
      (node (ref "U1") (pin "9") (pinfunction "VCCIO1_9") (pintype "power_in"))
      (node (ref "U1") (pin "94") (pinfunction "VCCIO2_94") (pintype "power_in"))
      (node (ref "XT1") (pin "1") (pinfunction "EN_1") (pintype "passive"))
      (node (ref "XT1") (pin "4") (pinfunction "VCC_4") (pintype "passive"))
    )
    (net (code "44") (name "24V") (class "Default")
      (node (ref "C1") (pin "1") (pinfunction "1_1") (pintype "passive"))
      (node (ref "C19") (pin "1") (pinfunction "1_1") (pintype "passive"))
      (node (ref "C2") (pin "1") (pinfunction "1_1") (pintype "passive"))
      (node (ref "C31") (pin "1") (pinfunction "1_1") (pintype "passive"))
      (node (ref "D5") (pin "K") (pinfunction "K_K") (pintype "passive"))
      (node (ref "D6") (pin "2") (pinfunction "2_2") (pintype "passive"))
      (node (ref "L1") (pin "1") (pinfunction "1_1") (pintype "passive"))
      (node (ref "L2") (pin "1") (pinfunction "1_1") (pintype "passive"))
      (node (ref "PS1") (pin "2") (pinfunction "+Vin_2") (pintype "passive"))
      (node (ref "X4") (pin "38") (pinfunction "38_38") (pintype "passive"))
      (node (ref "X4") (pin "40") (pinfunction "40_40") (pintype "passive"))
    )
    (net (code "45") (name "AGND") (class "Default")
      (node (ref "C46") (pin "2") (pinfunction "2_2") (pintype "passive"))
      (node (ref "C47") (pin "2") (pinfunction "2_2") (pintype "passive"))
      (node (ref "C48") (pin "2") (pinfunction "2_2") (pintype "passive"))
      (node (ref "C54") (pin "1") (pinfunction "1_1") (pintype "passive"))
      (node (ref "C55") (pin "1") (pinfunction "1_1") (pintype "passive"))
      (node (ref "C56") (pin "1") (pinfunction "1_1") (pintype "passive"))
      (node (ref "C66") (pin "1") (pinfunction "1_1") (pintype "passive"))
      (node (ref "C67") (pin "1") (pinfunction "1_1") (pintype "passive"))
      (node (ref "C68") (pin "1") (pinfunction "1_1") (pintype "passive"))
      (node (ref "PS2") (pin "4") (pinfunction "COM_4") (pintype "passive"))
      (node (ref "R41") (pin "2") (pinfunction "2_2") (pintype "passive"))
      (node (ref "U2") (pin "4") (pinfunction "GND_4") (pintype "power_in"))
      (node (ref "U3") (pin "4") (pinfunction "GND_4") (pintype "power_in"))
      (node (ref "U4") (pin "4") (pinfunction "GND_4") (pintype "power_in"))
      (node (ref "X4") (pin "27") (pinfunction "27_27") (pintype "passive"))
      (node (ref "X4") (pin "29") (pinfunction "29_29") (pintype "passive"))
      (node (ref "X4") (pin "31") (pinfunction "31_31") (pintype "passive"))
      (node (ref "X4") (pin "33") (pinfunction "33_33") (pintype "passive"))
      (node (ref "X4") (pin "35") (pinfunction "35_35") (pintype "passive"))
    )
    (net (code "46") (name "DGND") (class "Default")
      (node (ref "C11") (pin "2") (pinfunction "2_2") (pintype "passive"))
      (node (ref "C12") (pin "1") (pinfunction "1_1") (pintype "passive"))
      (node (ref "C13") (pin "2") (pinfunction "2_2") (pintype "passive"))
      (node (ref "C14") (pin "1") (pinfunction "1_1") (pintype "passive"))
      (node (ref "C15") (pin "2") (pinfunction "2_2") (pintype "passive"))
      (node (ref "C16") (pin "1") (pinfunction "1_1") (pintype "passive"))
      (node (ref "C17") (pin "1") (pinfunction "1_1") (pintype "passive"))
      (node (ref "C18") (pin "2") (pinfunction "2_2") (pintype "passive"))
      (node (ref "C21") (pin "2") (pinfunction "2_2") (pintype "passive"))
      (node (ref "C22") (pin "2") (pinfunction "2_2") (pintype "passive"))
      (node (ref "C23") (pin "2") (pinfunction "2_2") (pintype "passive"))
      (node (ref "C24") (pin "1") (pinfunction "1_1") (pintype "passive"))
      (node (ref "C25") (pin "1") (pinfunction "1_1") (pintype "passive"))
      (node (ref "C26") (pin "1") (pinfunction "1_1") (pintype "passive"))
      (node (ref "C27") (pin "2") (pinfunction "2_2") (pintype "passive"))
      (node (ref "C28") (pin "2") (pinfunction "2_2") (pintype "passive"))
      (node (ref "C29") (pin "2") (pinfunction "2_2") (pintype "passive"))
      (node (ref "C30") (pin "2") (pinfunction "2_2") (pintype "passive"))
      (node (ref "CASE GND") (pin "1") (pinfunction "1_1") (pintype "passive"))
      (node (ref "D3") (pin "1") (pinfunction "GND_1") (pintype "passive"))
      (node (ref "D4") (pin "3") (pinfunction "GND_3") (pintype "passive"))
      (node (ref "JTAG") (pin "10") (pinfunction "10_10") (pintype "passive"))
      (node (ref "JTAG") (pin "2") (pinfunction "2_2") (pintype "passive"))
      (node (ref "PS1") (pin "7") (pinfunction "-Vout_7") (pintype "passive"))
      (node (ref "R13") (pin "1") (pinfunction "1_1") (pintype "passive"))
      (node (ref "R17") (pin "1") (pinfunction "1_1") (pintype "passive"))
      (node (ref "R45") (pin "1") (pinfunction "1_1") (pintype "passive"))
      (node (ref "R5") (pin "1") (pinfunction "1_1") (pintype "passive"))
      (node (ref "R52") (pin "1") (pinfunction "1_1") (pintype "passive"))
      (node (ref "R53") (pin "1") (pinfunction "1_1") (pintype "passive"))
      (node (ref "R9") (pin "1") (pinfunction "1_1") (pintype "passive"))
      (node (ref "U1") (pin "10") (pinfunction "GNDIO_10") (pintype "power_in"))
      (node (ref "U1") (pin "11") (pinfunction "GNDINT_11") (pintype "power_in"))
      (node (ref "U1") (pin "32") (pinfunction "GNDIO_32") (pintype "power_in"))
      (node (ref "U1") (pin "37") (pinfunction "GNDINT_37") (pintype "power_in"))
      (node (ref "U1") (pin "46") (pinfunction "GNDIO_46") (pintype "power_in"))
      (node (ref "U1") (pin "60") (pinfunction "GNDIO_60") (pintype "power_in"))
      (node (ref "U1") (pin "65") (pinfunction "GNDINT_65") (pintype "power_in"))
      (node (ref "U1") (pin "79") (pinfunction "GNDIO_79") (pintype "power_in"))
      (node (ref "U1") (pin "90") (pinfunction "GNDINT_90") (pintype "power_in"))
      (node (ref "U1") (pin "93") (pinfunction "GNDIO_93") (pintype "power_in"))
      (node (ref "XT1") (pin "2") (pinfunction "GND_2") (pintype "passive"))
    )
    (net (code "47") (name "DGND_IN") (class "Default")
      (node (ref "C1") (pin "2") (pinfunction "2_2") (pintype "passive"))
      (node (ref "C19") (pin "2") (pinfunction "2_2") (pintype "passive"))
      (node (ref "C2") (pin "2") (pinfunction "2_2") (pintype "passive"))
      (node (ref "C31") (pin "2") (pinfunction "2_2") (pintype "passive"))
      (node (ref "D5") (pin "A") (pinfunction "A_A") (pintype "passive"))
      (node (ref "D6") (pin "1") (pinfunction "1_1") (pintype "passive"))
      (node (ref "L1") (pin "4") (pinfunction "4_4") (pintype "passive"))
      (node (ref "PS1") (pin "1") (pinfunction "-Vin_1") (pintype "passive"))
      (node (ref "X4") (pin "37") (pinfunction "37_37") (pintype "passive"))
      (node (ref "X4") (pin "39") (pinfunction "39_39") (pintype "passive"))
    )
    (net (code "48") (name "GND") (class "Default")
      (node (ref "L2") (pin "4") (pinfunction "4_4") (pintype "passive"))
    )
    (net (code "49") (name "GNDDR") (class "Default")
      (node (ref "C57") (pin "2") (pinfunction "2_2") (pintype "passive"))
      (node (ref "C58") (pin "2") (pinfunction "2_2") (pintype "passive"))
      (node (ref "C59") (pin "2") (pinfunction "2_2") (pintype "passive"))
      (node (ref "C60") (pin "2") (pinfunction "2_2") (pintype "passive"))
      (node (ref "OC1") (pin "2") (pinfunction "2_2") (pintype "passive"))
      (node (ref "OC2") (pin "2") (pinfunction "2_2") (pintype "passive"))
      (node (ref "OC3") (pin "2") (pinfunction "2_2") (pintype "passive"))
      (node (ref "OC4") (pin "2") (pinfunction "2_2") (pintype "passive"))
      (node (ref "OC9") (pin "3") (pinfunction "3_3") (pintype "passive"))
      (node (ref "PS3") (pin "5") (pinfunction "-Vout_5") (pintype "passive"))
      (node (ref "R51") (pin "2") (pinfunction "2_2") (pintype "passive"))
      (node (ref "X4") (pin "1") (pinfunction "1_1") (pintype "passive"))
      (node (ref "X4") (pin "11") (pinfunction "11_11") (pintype "passive"))
      (node (ref "X4") (pin "13") (pinfunction "13_13") (pintype "passive"))
      (node (ref "X4") (pin "15") (pinfunction "15_15") (pintype "passive"))
      (node (ref "X4") (pin "17") (pinfunction "17_17") (pintype "passive"))
      (node (ref "X4") (pin "19") (pinfunction "19_19") (pintype "passive"))
      (node (ref "X4") (pin "21") (pinfunction "21_21") (pintype "passive"))
      (node (ref "X4") (pin "3") (pinfunction "3_3") (pintype "passive"))
      (node (ref "X4") (pin "5") (pinfunction "5_5") (pintype "passive"))
      (node (ref "X4") (pin "7") (pinfunction "7_7") (pintype "passive"))
      (node (ref "X4") (pin "9") (pinfunction "9_9") (pintype "passive"))
    )
    (net (code "50") (name "Net-(D4-Y)") (class "Default")
      (node (ref "D4") (pin "4") (pinfunction "Y_4") (pintype "passive"))
      (node (ref "FO1") (pin "2") (pinfunction "2_2") (pintype "passive"))
    )
    (net (code "51") (name "Net-(FO1-Pad1)") (class "Default")
      (node (ref "FO1") (pin "1") (pinfunction "1_1") (pintype "passive"))
      (node (ref "R4") (pin "1") (pinfunction "1_1") (pintype "passive"))
    )
    (net (code "52") (name "Net-(OC1-Pad4)") (class "Default")
      (node (ref "OC1") (pin "4") (pinfunction "4_4") (pintype "passive"))
      (node (ref "R3") (pin "1") (pinfunction "1_1") (pintype "passive"))
    )
    (net (code "53") (name "Net-(OC2-Pad4)") (class "Default")
      (node (ref "OC2") (pin "4") (pinfunction "4_4") (pintype "passive"))
      (node (ref "R8") (pin "1") (pinfunction "1_1") (pintype "passive"))
    )
    (net (code "54") (name "Net-(OC3-Pad4)") (class "Default")
      (node (ref "OC3") (pin "4") (pinfunction "4_4") (pintype "passive"))
      (node (ref "R12") (pin "1") (pinfunction "1_1") (pintype "passive"))
    )
    (net (code "55") (name "Net-(OC4-Pad4)") (class "Default")
      (node (ref "OC4") (pin "4") (pinfunction "4_4") (pintype "passive"))
      (node (ref "R16") (pin "1") (pinfunction "1_1") (pintype "passive"))
    )
    (net (code "56") (name "Net-(OC7-Pad1)") (class "Default")
      (node (ref "OC7") (pin "1") (pinfunction "1_1") (pintype "passive"))
      (node (ref "R47") (pin "2") (pinfunction "2_2") (pintype "passive"))
      (node (ref "R48") (pin "2") (pinfunction "2_2") (pintype "passive"))
    )
    (net (code "57") (name "Net-(OC7-Pad4)") (class "Default")
      (node (ref "OC7") (pin "4") (pinfunction "4_4") (pintype "passive"))
      (node (ref "R46") (pin "1") (pinfunction "1_1") (pintype "passive"))
    )
    (net (code "58") (name "Net-(OC8-Pad1)") (class "Default")
      (node (ref "OC8") (pin "1") (pinfunction "1_1") (pintype "passive"))
      (node (ref "R55") (pin "2") (pinfunction "2_2") (pintype "passive"))
      (node (ref "R56") (pin "2") (pinfunction "2_2") (pintype "passive"))
    )
    (net (code "59") (name "Net-(OC8-Pad4)") (class "Default")
      (node (ref "OC8") (pin "4") (pinfunction "4_4") (pintype "passive"))
      (node (ref "R54") (pin "1") (pinfunction "1_1") (pintype "passive"))
    )
    (net (code "60") (name "Net-(OC9-Pad2)") (class "Default")
      (node (ref "OC9") (pin "2") (pinfunction "2_2") (pintype "passive"))
      (node (ref "R53") (pin "2") (pinfunction "2_2") (pintype "passive"))
    )
    (net (code "61") (name "Net-(PS2-+Vin)") (class "Default")
      (node (ref "C49") (pin "1") (pinfunction "1_1") (pintype "passive"))
      (node (ref "C50") (pin "1") (pinfunction "1_1") (pintype "passive"))
      (node (ref "C51") (pin "1") (pinfunction "1_1") (pintype "passive"))
      (node (ref "C52") (pin "1") (pinfunction "1_1") (pintype "passive"))
      (node (ref "C53") (pin "1") (pinfunction "1_1") (pintype "passive"))
      (node (ref "L1") (pin "2") (pinfunction "2_2") (pintype "passive"))
      (node (ref "PS2") (pin "1") (pinfunction "+Vin_1") (pintype "passive"))
    )
    (net (code "62") (name "Net-(PS2--Vin)") (class "Default")
      (node (ref "C49") (pin "2") (pinfunction "2_2") (pintype "passive"))
      (node (ref "C50") (pin "2") (pinfunction "2_2") (pintype "passive"))
      (node (ref "C51") (pin "2") (pinfunction "2_2") (pintype "passive"))
      (node (ref "C52") (pin "2") (pinfunction "2_2") (pintype "passive"))
      (node (ref "C53") (pin "2") (pinfunction "2_2") (pintype "passive"))
      (node (ref "L1") (pin "3") (pinfunction "3_3") (pintype "passive"))
      (node (ref "PS2") (pin "2") (pinfunction "-Vin_2") (pintype "passive"))
    )
    (net (code "63") (name "Net-(PS3-+Vin)") (class "Default")
      (node (ref "C61") (pin "1") (pinfunction "1_1") (pintype "passive"))
      (node (ref "C62") (pin "1") (pinfunction "1_1") (pintype "passive"))
      (node (ref "C63") (pin "1") (pinfunction "1_1") (pintype "passive"))
      (node (ref "C64") (pin "1") (pinfunction "1_1") (pintype "passive"))
      (node (ref "C65") (pin "1") (pinfunction "1_1") (pintype "passive"))
      (node (ref "L2") (pin "2") (pinfunction "2_2") (pintype "passive"))
      (node (ref "PS3") (pin "1") (pinfunction "+Vin_1") (pintype "passive"))
    )
    (net (code "64") (name "Net-(PS3--Vin)") (class "Default")
      (node (ref "C61") (pin "2") (pinfunction "2_2") (pintype "passive"))
      (node (ref "C62") (pin "2") (pinfunction "2_2") (pintype "passive"))
      (node (ref "C63") (pin "2") (pinfunction "2_2") (pintype "passive"))
      (node (ref "C64") (pin "2") (pinfunction "2_2") (pintype "passive"))
      (node (ref "C65") (pin "2") (pinfunction "2_2") (pintype "passive"))
      (node (ref "L2") (pin "3") (pinfunction "3_3") (pintype "passive"))
      (node (ref "PS3") (pin "2") (pinfunction "-Vin_2") (pintype "passive"))
    )
    (net (code "65") (name "Net-(U2-IN1)") (class "Default")
      (node (ref "R39") (pin "2") (pinfunction "2_2") (pintype "passive"))
      (node (ref "R40") (pin "1") (pinfunction "1_1") (pintype "passive"))
      (node (ref "U2") (pin "2") (pinfunction "IN1_2") (pintype "input"))
    )
    (net (code "66") (name "Net-(U2-IN2)") (class "Default")
      (node (ref "R40") (pin "2") (pinfunction "2_2") (pintype "passive"))
      (node (ref "R41") (pin "1") (pinfunction "1_1") (pintype "passive"))
      (node (ref "U2") (pin "3") (pinfunction "IN2_3") (pintype "input"))
    )
    (net (code "67") (name "Net-(U2-MS)") (class "Default")
      (node (ref "U2") (pin "1") (pinfunction "VREF_1") (pintype "output"))
      (node (ref "U2") (pin "7") (pinfunction "MS_7") (pintype "input"))
    )
    (net (code "68") (name "Net-(U3-IN1)") (class "Default")
      (node (ref "R42") (pin "2") (pinfunction "2_2") (pintype "passive"))
      (node (ref "R43") (pin "1") (pinfunction "1_1") (pintype "passive"))
      (node (ref "U3") (pin "2") (pinfunction "IN1_2") (pintype "input"))
    )
    (net (code "69") (name "Net-(U3-IN2)") (class "Default")
      (node (ref "R43") (pin "2") (pinfunction "2_2") (pintype "passive"))
      (node (ref "R44") (pin "1") (pinfunction "1_1") (pintype "passive"))
      (node (ref "U3") (pin "3") (pinfunction "IN2_3") (pintype "input"))
    )
    (net (code "70") (name "Net-(U3-MS)") (class "Default")
      (node (ref "R42") (pin "1") (pinfunction "1_1") (pintype "passive"))
      (node (ref "U3") (pin "1") (pinfunction "VREF_1") (pintype "output"))
      (node (ref "U3") (pin "7") (pinfunction "MS_7") (pintype "input"))
    )
    (net (code "71") (name "Net-(U4-IN1)") (class "Default")
      (node (ref "R49") (pin "2") (pinfunction "2_2") (pintype "passive"))
      (node (ref "R50") (pin "1") (pinfunction "1_1") (pintype "passive"))
      (node (ref "U4") (pin "2") (pinfunction "IN1_2") (pintype "input"))
    )
    (net (code "72") (name "Net-(U4-IN2)") (class "Default")
      (node (ref "R50") (pin "2") (pinfunction "2_2") (pintype "passive"))
      (node (ref "R51") (pin "1") (pinfunction "1_1") (pintype "passive"))
      (node (ref "U4") (pin "3") (pinfunction "IN2_3") (pintype "input"))
    )
    (net (code "73") (name "Net-(U4-MS)") (class "Default")
      (node (ref "U4") (pin "1") (pinfunction "VREF_1") (pintype "output"))
      (node (ref "U4") (pin "7") (pinfunction "MS_7") (pintype "input"))
    )
    (net (code "74") (name "VDD3V3") (class "Default")
      (node (ref "R12") (pin "2") (pinfunction "2_2") (pintype "passive"))
      (node (ref "R16") (pin "2") (pinfunction "2_2") (pintype "passive"))
      (node (ref "R3") (pin "2") (pinfunction "2_2") (pintype "passive"))
      (node (ref "R46") (pin "2") (pinfunction "2_2") (pintype "passive"))
      (node (ref "R54") (pin "2") (pinfunction "2_2") (pintype "passive"))
      (node (ref "R8") (pin "2") (pinfunction "2_2") (pintype "passive"))
    )
    (net (code "75") (name "unconnected-(FO1-NC-Pad3)") (class "Default")
      (node (ref "FO1") (pin "3") (pinfunction "NC_3") (pintype "passive"))
    )
    (net (code "76") (name "unconnected-(FO1-NC-Pad4)") (class "Default")
      (node (ref "FO1") (pin "4") (pinfunction "NC_4") (pintype "passive"))
    )
    (net (code "77") (name "unconnected-(JTAG-Pad6)") (class "Default")
      (node (ref "JTAG") (pin "6") (pinfunction "6_6") (pintype "passive"))
    )
    (net (code "78") (name "unconnected-(JTAG-Pad7)") (class "Default")
      (node (ref "JTAG") (pin "7") (pinfunction "7_7") (pintype "passive"))
    )
    (net (code "79") (name "unconnected-(JTAG-Pad8)") (class "Default")
      (node (ref "JTAG") (pin "8") (pinfunction "8_8") (pintype "passive"))
    )
    (net (code "80") (name "unconnected-(PS1-NC-Pad5)") (class "Default")
      (node (ref "PS1") (pin "5") (pinfunction "NC_5") (pintype "passive"))
    )
    (net (code "81") (name "unconnected-(PS1-NC-Pad8)") (class "Default")
      (node (ref "PS1") (pin "8") (pinfunction "NC_8") (pintype "passive"))
    )
    (net (code "82") (name "unconnected-(PS1-On{slash}Off-Pad3)") (class "Default")
      (node (ref "PS1") (pin "3") (pinfunction "On/Off_3") (pintype "passive"))
    )
    (net (code "83") (name "unconnected-(U1A-IO-Pad2)") (class "Default")
      (node (ref "U1") (pin "2") (pinfunction "IO_2") (pintype "bidirectional"))
    )
    (net (code "84") (name "unconnected-(U1A-IO-Pad3)") (class "Default")
      (node (ref "U1") (pin "3") (pinfunction "IO_3") (pintype "bidirectional"))
    )
    (net (code "85") (name "unconnected-(U1A-IO-Pad4)") (class "Default")
      (node (ref "U1") (pin "4") (pinfunction "IO_4") (pintype "bidirectional"))
    )
    (net (code "86") (name "unconnected-(U1A-IO-Pad5)") (class "Default")
      (node (ref "U1") (pin "5") (pinfunction "IO_5") (pintype "bidirectional"))
    )
    (net (code "87") (name "unconnected-(U1A-IO-Pad6)") (class "Default")
      (node (ref "U1") (pin "6") (pinfunction "IO_6") (pintype "bidirectional"))
    )
    (net (code "88") (name "unconnected-(U1A-IO-Pad7)") (class "Default")
      (node (ref "U1") (pin "7") (pinfunction "IO_7") (pintype "bidirectional"))
    )
    (net (code "89") (name "unconnected-(U1A-IO-Pad8)") (class "Default")
      (node (ref "U1") (pin "8") (pinfunction "IO_8") (pintype "bidirectional"))
    )
    (net (code "90") (name "unconnected-(U1A-IO-Pad15)") (class "Default")
      (node (ref "U1") (pin "15") (pinfunction "IO_15") (pintype "bidirectional"))
    )
    (net (code "91") (name "unconnected-(U1A-IO-Pad16)") (class "Default")
      (node (ref "U1") (pin "16") (pinfunction "IO_16") (pintype "bidirectional"))
    )
    (net (code "92") (name "unconnected-(U1A-IO-Pad18)") (class "Default")
      (node (ref "U1") (pin "18") (pinfunction "IO_18") (pintype "bidirectional"))
    )
    (net (code "93") (name "unconnected-(U1A-IO-Pad19)") (class "Default")
      (node (ref "U1") (pin "19") (pinfunction "IO_19") (pintype "bidirectional"))
    )
    (net (code "94") (name "unconnected-(U1A-IO-Pad20)") (class "Default")
      (node (ref "U1") (pin "20") (pinfunction "IO_20") (pintype "bidirectional"))
    )
    (net (code "95") (name "unconnected-(U1A-IO-Pad21)") (class "Default")
      (node (ref "U1") (pin "21") (pinfunction "IO_21") (pintype "bidirectional"))
    )
    (net (code "96") (name "unconnected-(U1A-IO-Pad26)") (class "Default")
      (node (ref "U1") (pin "26") (pinfunction "IO_26") (pintype "bidirectional"))
    )
    (net (code "97") (name "unconnected-(U1A-IO-Pad27)") (class "Default")
      (node (ref "U1") (pin "27") (pinfunction "IO_27") (pintype "bidirectional"))
    )
    (net (code "98") (name "unconnected-(U1A-IO-Pad28)") (class "Default")
      (node (ref "U1") (pin "28") (pinfunction "IO_28") (pintype "bidirectional"))
    )
    (net (code "99") (name "unconnected-(U1A-IO-Pad34)") (class "Default")
      (node (ref "U1") (pin "34") (pinfunction "IO_34") (pintype "bidirectional"))
    )
    (net (code "100") (name "unconnected-(U1A-IO-Pad35)") (class "Default")
      (node (ref "U1") (pin "35") (pinfunction "IO_35") (pintype "bidirectional"))
    )
    (net (code "101") (name "unconnected-(U1A-IO-Pad36)") (class "Default")
      (node (ref "U1") (pin "36") (pinfunction "IO_36") (pintype "bidirectional"))
    )
    (net (code "102") (name "unconnected-(U1A-IO-Pad38)") (class "Default")
      (node (ref "U1") (pin "38") (pinfunction "IO_38") (pintype "bidirectional"))
    )
    (net (code "103") (name "unconnected-(U1A-IO-Pad40)") (class "Default")
      (node (ref "U1") (pin "40") (pinfunction "IO_40") (pintype "bidirectional"))
    )
    (net (code "104") (name "unconnected-(U1A-IO-Pad41)") (class "Default")
      (node (ref "U1") (pin "41") (pinfunction "IO_41") (pintype "bidirectional"))
    )
    (net (code "105") (name "unconnected-(U1A-IO-Pad42)") (class "Default")
      (node (ref "U1") (pin "42") (pinfunction "IO_42") (pintype "bidirectional"))
    )
    (net (code "106") (name "unconnected-(U1A-IO-Pad47)") (class "Default")
      (node (ref "U1") (pin "47") (pinfunction "IO_47") (pintype "bidirectional"))
    )
    (net (code "107") (name "unconnected-(U1A-IO{slash}DEV_CLRn-Pad44)") (class "Default")
      (node (ref "U1") (pin "44") (pinfunction "IO/DEV_CLRn_44") (pintype "bidirectional"))
    )
    (net (code "108") (name "unconnected-(U1A-IO{slash}GCLK0-Pad12)") (class "Default")
      (node (ref "U1") (pin "12") (pinfunction "IO/GCLK0_12") (pintype "bidirectional"))
    )
    (net (code "109") (name "unconnected-(U1B-IO-Pad1)") (class "Default")
      (node (ref "U1") (pin "1") (pinfunction "IO_1") (pintype "bidirectional"))
    )
    (net (code "110") (name "unconnected-(U1B-IO-Pad52)") (class "Default")
      (node (ref "U1") (pin "52") (pinfunction "IO_52") (pintype "bidirectional"))
    )
    (net (code "111") (name "unconnected-(U1B-IO-Pad53)") (class "Default")
      (node (ref "U1") (pin "53") (pinfunction "IO_53") (pintype "bidirectional"))
    )
    (net (code "112") (name "unconnected-(U1B-IO-Pad54)") (class "Default")
      (node (ref "U1") (pin "54") (pinfunction "IO_54") (pintype "bidirectional"))
    )
    (net (code "113") (name "unconnected-(U1B-IO-Pad55)") (class "Default")
      (node (ref "U1") (pin "55") (pinfunction "IO_55") (pintype "bidirectional"))
    )
    (net (code "114") (name "unconnected-(U1B-IO-Pad56)") (class "Default")
      (node (ref "U1") (pin "56") (pinfunction "IO_56") (pintype "bidirectional"))
    )
    (net (code "115") (name "unconnected-(U1B-IO-Pad57)") (class "Default")
      (node (ref "U1") (pin "57") (pinfunction "IO_57") (pintype "bidirectional"))
    )
    (net (code "116") (name "unconnected-(U1B-IO-Pad58)") (class "Default")
      (node (ref "U1") (pin "58") (pinfunction "IO_58") (pintype "bidirectional"))
    )
    (net (code "117") (name "unconnected-(U1B-IO-Pad61)") (class "Default")
      (node (ref "U1") (pin "61") (pinfunction "IO_61") (pintype "bidirectional"))
    )
    (net (code "118") (name "unconnected-(U1B-IO-Pad66)") (class "Default")
      (node (ref "U1") (pin "66") (pinfunction "IO_66") (pintype "bidirectional"))
    )
    (net (code "119") (name "unconnected-(U1B-IO-Pad67)") (class "Default")
      (node (ref "U1") (pin "67") (pinfunction "IO_67") (pintype "bidirectional"))
    )
    (net (code "120") (name "unconnected-(U1B-IO-Pad68)") (class "Default")
      (node (ref "U1") (pin "68") (pinfunction "IO_68") (pintype "bidirectional"))
    )
    (net (code "121") (name "unconnected-(U1B-IO-Pad69)") (class "Default")
      (node (ref "U1") (pin "69") (pinfunction "IO_69") (pintype "bidirectional"))
    )
    (net (code "122") (name "unconnected-(U1B-IO-Pad70)") (class "Default")
      (node (ref "U1") (pin "70") (pinfunction "IO_70") (pintype "bidirectional"))
    )
    (net (code "123") (name "unconnected-(U1B-IO-Pad71)") (class "Default")
      (node (ref "U1") (pin "71") (pinfunction "IO_71") (pintype "bidirectional"))
    )
    (net (code "124") (name "unconnected-(U1B-IO-Pad72)") (class "Default")
      (node (ref "U1") (pin "72") (pinfunction "IO_72") (pintype "bidirectional"))
    )
    (net (code "125") (name "unconnected-(U1B-IO-Pad73)") (class "Default")
      (node (ref "U1") (pin "73") (pinfunction "IO_73") (pintype "bidirectional"))
    )
    (net (code "126") (name "unconnected-(U1B-IO-Pad74)") (class "Default")
      (node (ref "U1") (pin "74") (pinfunction "IO_74") (pintype "bidirectional"))
    )
    (net (code "127") (name "unconnected-(U1B-IO-Pad75)") (class "Default")
      (node (ref "U1") (pin "75") (pinfunction "IO_75") (pintype "bidirectional"))
    )
    (net (code "128") (name "unconnected-(U1B-IO-Pad76)") (class "Default")
      (node (ref "U1") (pin "76") (pinfunction "IO_76") (pintype "bidirectional"))
    )
    (net (code "129") (name "unconnected-(U1B-IO-Pad77)") (class "Default")
      (node (ref "U1") (pin "77") (pinfunction "IO_77") (pintype "bidirectional"))
    )
    (net (code "130") (name "unconnected-(U1B-IO-Pad78)") (class "Default")
      (node (ref "U1") (pin "78") (pinfunction "IO_78") (pintype "bidirectional"))
    )
    (net (code "131") (name "unconnected-(U1B-IO-Pad81)") (class "Default")
      (node (ref "U1") (pin "81") (pinfunction "IO_81") (pintype "bidirectional"))
    )
    (net (code "132") (name "unconnected-(U1B-IO-Pad82)") (class "Default")
      (node (ref "U1") (pin "82") (pinfunction "IO_82") (pintype "bidirectional"))
    )
    (net (code "133") (name "unconnected-(U1B-IO-Pad83)") (class "Default")
      (node (ref "U1") (pin "83") (pinfunction "IO_83") (pintype "bidirectional"))
    )
    (net (code "134") (name "unconnected-(U1B-IO-Pad84)") (class "Default")
      (node (ref "U1") (pin "84") (pinfunction "IO_84") (pintype "bidirectional"))
    )
    (net (code "135") (name "unconnected-(U1B-IO-Pad97)") (class "Default")
      (node (ref "U1") (pin "97") (pinfunction "IO_97") (pintype "bidirectional"))
    )
    (net (code "136") (name "unconnected-(U1B-IO-Pad98)") (class "Default")
      (node (ref "U1") (pin "98") (pinfunction "IO_98") (pintype "bidirectional"))
    )
    (net (code "137") (name "unconnected-(U1B-IO-Pad99)") (class "Default")
      (node (ref "U1") (pin "99") (pinfunction "IO_99") (pintype "bidirectional"))
    )
    (net (code "138") (name "unconnected-(U1B-IO{slash}GCLK3-Pad64)") (class "Default")
      (node (ref "U1") (pin "64") (pinfunction "IO/GCLK3_64") (pintype "bidirectional"))
    )
    (net (code "139") (name "unconnected-(X4-Pad14)") (class "Default")
      (node (ref "X4") (pin "14") (pinfunction "14_14") (pintype "passive"))
    )
    (net (code "140") (name "unconnected-(X4-Pad16)") (class "Default")
      (node (ref "X4") (pin "16") (pinfunction "16_16") (pintype "passive"))
    )
    (net (code "141") (name "unconnected-(X4-Pad18)") (class "Default")
      (node (ref "X4") (pin "18") (pinfunction "18_18") (pintype "passive"))
    )
    (net (code "142") (name "unconnected-(X4-Pad20)") (class "Default")
      (node (ref "X4") (pin "20") (pinfunction "20_20") (pintype "passive"))
    )
    (net (code "143") (name "unconnected-(X4-Pad36)") (class "Default")
      (node (ref "X4") (pin "36") (pinfunction "36_36") (pintype "passive"))
    )
  )
)
